# USB_Host_Hub_TypeC_DRP.net
KiCad netlist of a schematic drawn in Altium Designer
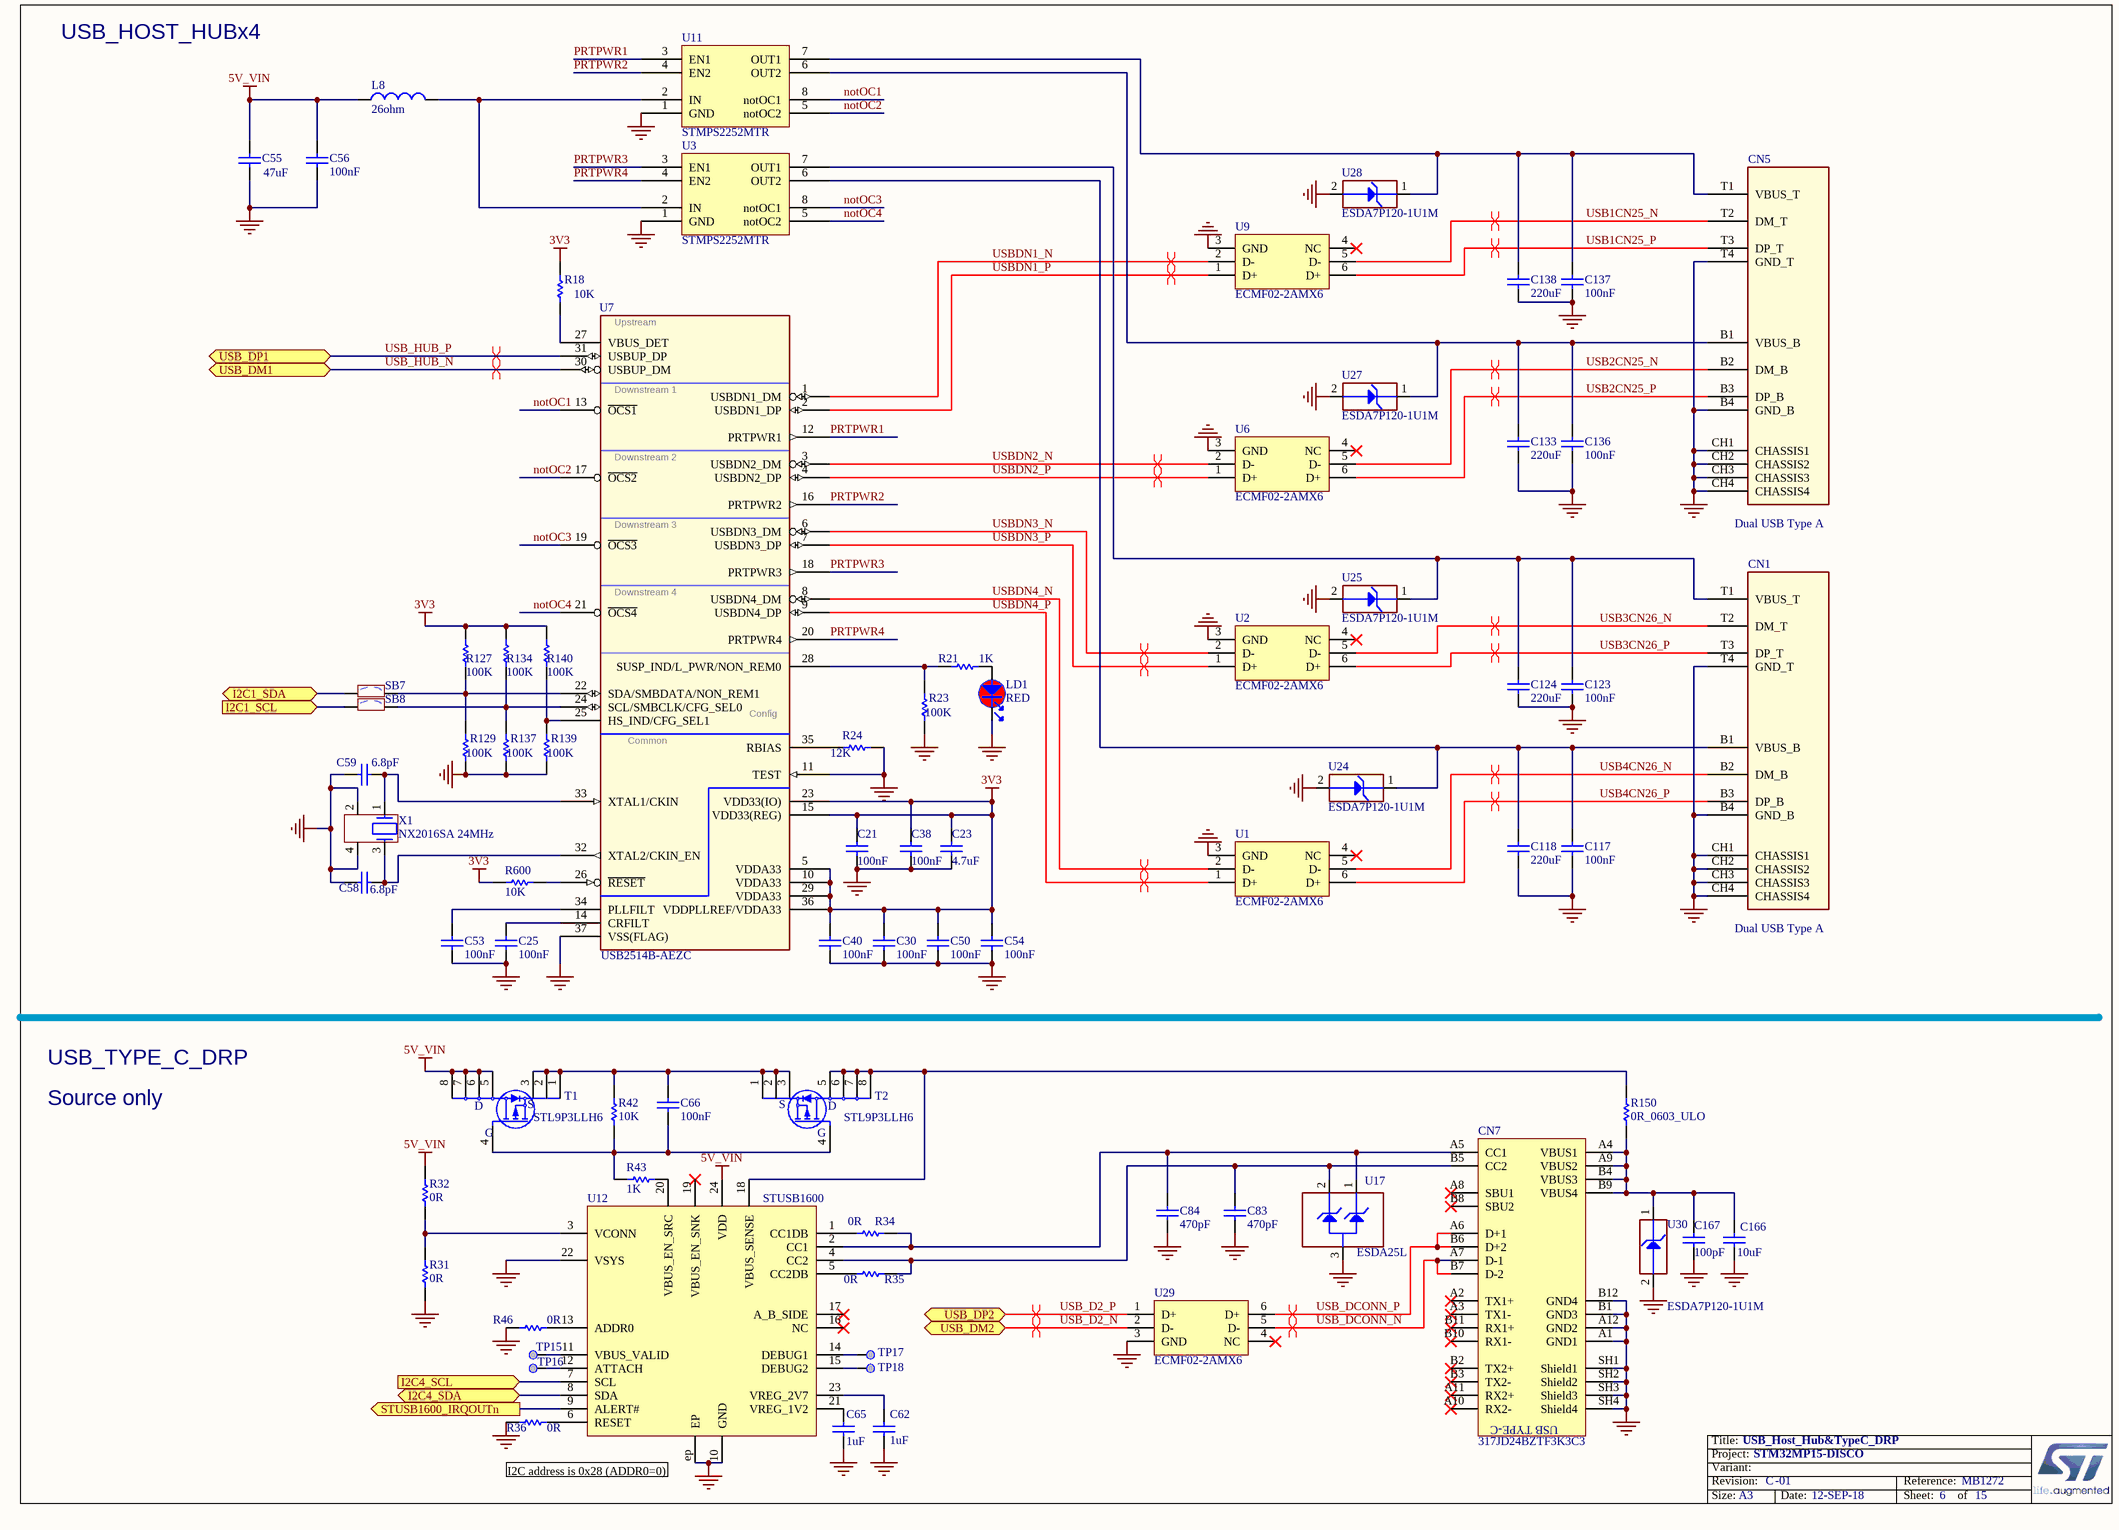
[diagram p0: USB_Host_Hub&TypeC_DRP.SchDoc]

(export (version "E")
  (design (tool "Eeschema 10.0.6"))
  (components
    (comp (ref "C21")
      (value "100nF")
      (footprint "C0402")
      (description "Capacitor, MLCC, 100nF, 16V, X7R, 10%, 0402, T=0,5mm")
      (fields
        (field (name "INTERNAL_PART_NUMBER") "MCD-00102")
        (field (name "MANUFACTURER_PART_NUMBER") "CC0402KRX7R7BB104")
        (field (name "PROVIDED_BY") "SUBCO")
      )
      (libsource (lib "MCD_PARTS_database") (part "Capacitor"))
    )
    (comp (ref "C23")
      (value "4.7uF")
      (footprint "C0402")
      (description "Capacitor, MLCC, 4.7uF, 6V3, X5R, 20%, 0402, T=0,5mm")
      (fields
        (field (name "INTERNAL_PART_NUMBER") "MCD-01356")
        (field (name "MANUFACTURER_PART_NUMBER") "GRM155R60J475ME47")
        (field (name "PROVIDED_BY") "SUBCO")
      )
      (libsource (lib "MCD_PARTS_database") (part "Capacitor"))
    )
    (comp (ref "C25")
      (value "100nF")
      (footprint "C0402")
      (description "Capacitor, MLCC, 100nF, 16V, X7R, 10%, 0402, T=0,5mm")
      (fields
        (field (name "INTERNAL_PART_NUMBER") "MCD-00102")
        (field (name "MANUFACTURER_PART_NUMBER") "CC0402KRX7R7BB104")
        (field (name "PROVIDED_BY") "SUBCO")
      )
      (libsource (lib "MCD_PARTS_database") (part "Capacitor"))
    )
    (comp (ref "C30")
      (value "100nF")
      (footprint "C0402")
      (description "Capacitor, MLCC, 100nF, 16V, X7R, 10%, 0402, T=0,5mm")
      (fields
        (field (name "INTERNAL_PART_NUMBER") "MCD-00102")
        (field (name "MANUFACTURER_PART_NUMBER") "CC0402KRX7R7BB104")
        (field (name "PROVIDED_BY") "SUBCO")
      )
      (libsource (lib "MCD_PARTS_database") (part "Capacitor"))
    )
    (comp (ref "C38")
      (value "100nF")
      (footprint "C0402")
      (description "Capacitor, MLCC, 100nF, 16V, X7R, 10%, 0402, T=0,5mm")
      (fields
        (field (name "INTERNAL_PART_NUMBER") "MCD-00102")
        (field (name "MANUFACTURER_PART_NUMBER") "CC0402KRX7R7BB104")
        (field (name "PROVIDED_BY") "SUBCO")
      )
      (libsource (lib "MCD_PARTS_database") (part "Capacitor"))
    )
    (comp (ref "C40")
      (value "100nF")
      (footprint "C0402")
      (description "Capacitor, MLCC, 100nF, 16V, X7R, 10%, 0402, T=0,5mm")
      (fields
        (field (name "INTERNAL_PART_NUMBER") "MCD-00102")
        (field (name "MANUFACTURER_PART_NUMBER") "CC0402KRX7R7BB104")
        (field (name "PROVIDED_BY") "SUBCO")
      )
      (libsource (lib "MCD_PARTS_database") (part "Capacitor"))
    )
    (comp (ref "C50")
      (value "100nF")
      (footprint "C0402")
      (description "Capacitor, MLCC, 100nF, 16V, X7R, 10%, 0402, T=0,5mm")
      (fields
        (field (name "INTERNAL_PART_NUMBER") "MCD-00102")
        (field (name "MANUFACTURER_PART_NUMBER") "CC0402KRX7R7BB104")
        (field (name "PROVIDED_BY") "SUBCO")
      )
      (libsource (lib "MCD_PARTS_database") (part "Capacitor"))
    )
    (comp (ref "C53")
      (value "100nF")
      (footprint "C0402")
      (description "Capacitor, MLCC, 100nF, 16V, X7R, 10%, 0402, T=0,5mm")
      (fields
        (field (name "INTERNAL_PART_NUMBER") "MCD-00102")
        (field (name "MANUFACTURER_PART_NUMBER") "CC0402KRX7R7BB104")
        (field (name "PROVIDED_BY") "SUBCO")
      )
      (libsource (lib "MCD_PARTS_database") (part "Capacitor"))
    )
    (comp (ref "C54")
      (value "100nF")
      (footprint "C0402")
      (description "Capacitor, MLCC, 100nF, 16V, X7R, 10%, 0402, T=0,5mm")
      (fields
        (field (name "INTERNAL_PART_NUMBER") "MCD-00102")
        (field (name "MANUFACTURER_PART_NUMBER") "CC0402KRX7R7BB104")
        (field (name "PROVIDED_BY") "SUBCO")
      )
      (libsource (lib "MCD_PARTS_database") (part "Capacitor"))
    )
    (comp (ref "C55")
      (value "47uF")
      (footprint "C0805")
      (description "Capacitor, MLCC, 47uF, 10V, X5R, 20%, 0805, T=1,25mm")
      (fields
        (field (name "INTERNAL_PART_NUMBER") "MCD-00204")
        (field (name "MANUFACTURER_PART_NUMBER") "GRM21BR61A476ME15K")
        (field (name "PROVIDED_BY") "SUBCO")
      )
      (libsource (lib "MCD_PARTS_database") (part "Capacitor"))
    )
    (comp (ref "C56")
      (value "100nF")
      (footprint "C0402")
      (description "Capacitor, MLCC, 100nF, 16V, X7R, 10%, 0402, T=0,5mm")
      (fields
        (field (name "INTERNAL_PART_NUMBER") "MCD-00102")
        (field (name "MANUFACTURER_PART_NUMBER") "CC0402KRX7R7BB104")
        (field (name "PROVIDED_BY") "SUBCO")
      )
      (libsource (lib "MCD_PARTS_database") (part "Capacitor"))
    )
    (comp (ref "C58")
      (value "6.8pF")
      (footprint "C0402")
      (description "Capacitor, MLCC, 6.8pF, 50V, NPO, +-0.25pF, 0402, T=0.5mm")
      (fields
        (field (name "INTERNAL_PART_NUMBER") "MCD-00674")
        (field (name "MANUFACTURER_PART_NUMBER") "CC0402CRNPO9BN6R8")
        (field (name "PROVIDED_BY") "SUBCO")
      )
      (libsource (lib "MCD_PARTS_database") (part "Capacitor"))
    )
    (comp (ref "C59")
      (value "6.8pF")
      (footprint "C0402")
      (description "Capacitor, MLCC, 6.8pF, 50V, NPO, +-0.25pF, 0402, T=0.5mm")
      (fields
        (field (name "INTERNAL_PART_NUMBER") "MCD-00674")
        (field (name "MANUFACTURER_PART_NUMBER") "CC0402CRNPO9BN6R8")
        (field (name "PROVIDED_BY") "SUBCO")
      )
      (libsource (lib "MCD_PARTS_database") (part "Capacitor"))
    )
    (comp (ref "C62")
      (value "1uF")
      (footprint "C0402")
      (description "Capacitor, MLCC, 1uF, 6V3, X5R, 10%, 0402, T=0,5mm")
      (fields
        (field (name "INTERNAL_PART_NUMBER") "MCD-00095")
        (field (name "MANUFACTURER_PART_NUMBER") "GRM155R61E105KA12")
        (field (name "PROVIDED_BY") "SUBCO")
      )
      (libsource (lib "MCD_PARTS_database") (part "Capacitor"))
    )
    (comp (ref "C65")
      (value "1uF")
      (footprint "C0402")
      (description "Capacitor, MLCC, 1uF, 6V3, X5R, 10%, 0402, T=0,5mm")
      (fields
        (field (name "INTERNAL_PART_NUMBER") "MCD-00095")
        (field (name "MANUFACTURER_PART_NUMBER") "GRM155R61E105KA12")
        (field (name "PROVIDED_BY") "SUBCO")
      )
      (libsource (lib "MCD_PARTS_database") (part "Capacitor"))
    )
    (comp (ref "C66")
      (value "100nF")
      (footprint "C0402")
      (description "Capacitor, MLCC, 100nF, 16V, X7R, 10%, 0402, T=0,5mm")
      (fields
        (field (name "INTERNAL_PART_NUMBER") "MCD-00102")
        (field (name "MANUFACTURER_PART_NUMBER") "CC0402KRX7R7BB104")
        (field (name "PROVIDED_BY") "SUBCO")
      )
      (libsource (lib "MCD_PARTS_database") (part "Capacitor"))
    )
    (comp (ref "C83")
      (value "470pF")
      (footprint "C0402")
      (description "Capacitor, MLCC, 470pF, 50V, NPO, 5%, 0402, T=0,5mm")
      (fields
        (field (name "INTERNAL_PART_NUMBER") "MCD-00724")
        (field (name "MANUFACTURER_PART_NUMBER") "CC0402JRNPO9BN471")
        (field (name "PROVIDED_BY") "SUBCO")
      )
      (libsource (lib "MCD_PARTS_database") (part "Capacitor"))
    )
    (comp (ref "C84")
      (value "470pF")
      (footprint "C0402")
      (description "Capacitor, MLCC, 470pF, 50V, NPO, 5%, 0402, T=0,5mm")
      (fields
        (field (name "INTERNAL_PART_NUMBER") "MCD-00724")
        (field (name "MANUFACTURER_PART_NUMBER") "CC0402JRNPO9BN471")
        (field (name "PROVIDED_BY") "SUBCO")
      )
      (libsource (lib "MCD_PARTS_database") (part "Capacitor"))
    )
    (comp (ref "C117")
      (value "100nF")
      (footprint "C0402")
      (description "Capacitor, MLCC, 100nF, 16V, X7R, 10%, 0402, T=0,5mm")
      (fields
        (field (name "INTERNAL_PART_NUMBER") "MCD-00102")
        (field (name "MANUFACTURER_PART_NUMBER") "CC0402KRX7R7BB104")
        (field (name "PROVIDED_BY") "SUBCO")
      )
      (libsource (lib "MCD_PARTS_database") (part "Capacitor"))
    )
    (comp (ref "C118")
      (value "220uF")
      (footprint "C1206_H1P6")
      (description "Capacitor, MLCC, 220uF, 6V3, X5R, 20%, 1206, T=1,6mm")
      (fields
        (field (name "INTERNAL_PART_NUMBER") "MCD-00104")
        (field (name "MANUFACTURER_PART_NUMBER") "GRM31CR60J227ME11")
        (field (name "PROVIDED_BY") "SUBCO")
      )
      (libsource (lib "MCD_PARTS_database") (part "Capacitor"))
    )
    (comp (ref "C123")
      (value "100nF")
      (footprint "C0402")
      (description "Capacitor, MLCC, 100nF, 16V, X7R, 10%, 0402, T=0,5mm")
      (fields
        (field (name "INTERNAL_PART_NUMBER") "MCD-00102")
        (field (name "MANUFACTURER_PART_NUMBER") "CC0402KRX7R7BB104")
        (field (name "PROVIDED_BY") "SUBCO")
      )
      (libsource (lib "MCD_PARTS_database") (part "Capacitor"))
    )
    (comp (ref "C124")
      (value "220uF")
      (footprint "C1206_H1P6")
      (description "Capacitor, MLCC, 220uF, 6V3, X5R, 20%, 1206, T=1,6mm")
      (fields
        (field (name "INTERNAL_PART_NUMBER") "MCD-00104")
        (field (name "MANUFACTURER_PART_NUMBER") "GRM31CR60J227ME11")
        (field (name "PROVIDED_BY") "SUBCO")
      )
      (libsource (lib "MCD_PARTS_database") (part "Capacitor"))
    )
    (comp (ref "C133")
      (value "220uF")
      (footprint "C1206_H1P6")
      (description "Capacitor, MLCC, 220uF, 6V3, X5R, 20%, 1206, T=1,6mm")
      (fields
        (field (name "INTERNAL_PART_NUMBER") "MCD-00104")
        (field (name "MANUFACTURER_PART_NUMBER") "GRM31CR60J227ME11")
        (field (name "PROVIDED_BY") "SUBCO")
      )
      (libsource (lib "MCD_PARTS_database") (part "Capacitor"))
    )
    (comp (ref "C136")
      (value "100nF")
      (footprint "C0402")
      (description "Capacitor, MLCC, 100nF, 16V, X7R, 10%, 0402, T=0,5mm")
      (fields
        (field (name "INTERNAL_PART_NUMBER") "MCD-00102")
        (field (name "MANUFACTURER_PART_NUMBER") "CC0402KRX7R7BB104")
        (field (name "PROVIDED_BY") "SUBCO")
      )
      (libsource (lib "MCD_PARTS_database") (part "Capacitor"))
    )
    (comp (ref "C137")
      (value "100nF")
      (footprint "C0402")
      (description "Capacitor, MLCC, 100nF, 16V, X7R, 10%, 0402, T=0,5mm")
      (fields
        (field (name "INTERNAL_PART_NUMBER") "MCD-00102")
        (field (name "MANUFACTURER_PART_NUMBER") "CC0402KRX7R7BB104")
        (field (name "PROVIDED_BY") "SUBCO")
      )
      (libsource (lib "MCD_PARTS_database") (part "Capacitor"))
    )
    (comp (ref "C138")
      (value "220uF")
      (footprint "C1206_H1P6")
      (description "Capacitor, MLCC, 220uF, 6V3, X5R, 20%, 1206, T=1,6mm")
      (fields
        (field (name "INTERNAL_PART_NUMBER") "MCD-00104")
        (field (name "MANUFACTURER_PART_NUMBER") "GRM31CR60J227ME11")
        (field (name "PROVIDED_BY") "SUBCO")
      )
      (libsource (lib "MCD_PARTS_database") (part "Capacitor"))
    )
    (comp (ref "C166")
      (value "10uF")
      (footprint "C0805")
      (description "Capacitor, MLCC, 10uF, 25V, X5R, 10%, 0805, T=0,85mm")
      (fields
        (field (name "INTERNAL_PART_NUMBER") "MCD-00014")
        (field (name "MANUFACTURER_PART_NUMBER") "CC0805KRX5R8BB106")
        (field (name "PROVIDED_BY") "SUBCO")
      )
      (libsource (lib "MCD_PARTS_database") (part "Capacitor"))
    )
    (comp (ref "C167")
      (value "100pF")
      (footprint "C0402")
      (description "Capacitor, MLCC, 100pF, 50V, NPO, 5%, 0402, T=0,5mm")
      (fields
        (field (name "INTERNAL_PART_NUMBER") "MCD-00205")
        (field (name "MANUFACTURER_PART_NUMBER") "CC0402JRNPO9BN101")
        (field (name "PROVIDED_BY") "SUBCO")
      )
      (libsource (lib "MCD_PARTS_database") (part "Capacitor"))
    )
    (comp (ref "CN1")
      (value "Dual USB Type A")
      (footprint "CON_DUAL-USB-TYPE-A_CONEXCON_5600-3081")
      (description "USB-Receptacle,Dual-Type-A, RA, TH, Height 15.5mm")
      (fields
        (field (name "INTERNAL_PART_NUMBER") "MCD-00109")
        (field (name "MANUFACTURER_PART_NUMBER") "5600-3081")
        (field (name "PROVIDED_BY") "SUBCO")
      )
      (libsource (lib "MCD_PARTS_database") (part "USB_DUAL_TYPEA_5600-3081"))
    )
    (comp (ref "CN5")
      (value "Dual USB Type A")
      (footprint "CON_DUAL-USB-TYPE-A_CONEXCON_5600-3081")
      (description "USB-Receptacle,Dual-Type-A, RA, TH, Height 15.5mm")
      (fields
        (field (name "INTERNAL_PART_NUMBER") "MCD-00109")
        (field (name "MANUFACTURER_PART_NUMBER") "5600-3081")
        (field (name "PROVIDED_BY") "SUBCO")
      )
      (libsource (lib "MCD_PARTS_database") (part "USB_DUAL_TYPEA_5600-3081"))
    )
    (comp (ref "CN7")
      (value "317JD24BZTF3K3C3")
      (footprint "CON_USB-TYPEC_COXOC_317JD24BZTF3K3C3")
      (description "USB tyce C certified receptacle for 1.6mm pcb height")
      (fields
        (field (name "INTERNAL_PART_NUMBER") "MCD-01108")
        (field (name "MANUFACTURER") "CHANT SINCERE (COXOC)")
        (field (name "PROVIDED_BY") "SUBCO")
      )
      (libsource (lib "MCD_PARTS_database") (part "USB_TYPE_C_Receptacle_317JD24BZTF3K3C3"))
    )
    (comp (ref "L8")
      (value "26ohm")
      (footprint "FIL_0603_H0P65")
      (description "Bead,26R at 100Mhz,6A,0603")
      (fields
        (field (name "INTERNAL_PART_NUMBER") "MCD-00305")
        (field (name "MANUFACTURER_PART_NUMBER") "BLM18KG260TN1")
        (field (name "PROVIDED_BY") "SUBCO")
      )
      (libsource (lib "MCD_PARTS_database") (part "BEAD"))
    )
    (comp (ref "LD1")
      (value "RED")
      (footprint "LED_0603_RED")
      (description "LED, Red, 0603")
      (fields
        (field (name "INTERNAL_PART_NUMBER") "MCD-00049")
        (field (name "MANUFACTURER_PART_NUMBER") "19-213-R6C-AP1Q2B/3T")
        (field (name "PROVIDED_BY") "SUBCO")
      )
      (libsource (lib "MCD_PARTS_database") (part "LED_red"))
    )
    (comp (ref "R18")
      (value "10K")
      (footprint "R0402")
      (description "Resistor,10K,0402,1%,1/16W")
      (fields
        (field (name "INTERNAL_PART_NUMBER") "MCD-00053")
        (field (name "MANUFACTURER_PART_NUMBER") "RC0402FR-0710KL")
        (field (name "PROVIDED_BY") "SUBCO")
      )
      (libsource (lib "MCD_PARTS_database") (part "Resistor"))
    )
    (comp (ref "R21")
      (value "1K")
      (footprint "R0402")
      (description "Resistor,1K,0402,1%,1/16W")
      (fields
        (field (name "INTERNAL_PART_NUMBER") "MCD-00061")
        (field (name "MANUFACTURER_PART_NUMBER") "RC0402FR-071KL")
        (field (name "PROVIDED_BY") "SUBCO")
      )
      (libsource (lib "MCD_PARTS_database") (part "Resistor"))
    )
    (comp (ref "R23")
      (value "100K")
      (footprint "R0402")
      (description "Resistor,100K,0402,1%,1/16W")
      (fields
        (field (name "INTERNAL_PART_NUMBER") "MCD-00059")
        (field (name "MANUFACTURER_PART_NUMBER") "RC0402FR-07100KL")
        (field (name "PROVIDED_BY") "SUBCO")
      )
      (libsource (lib "MCD_PARTS_database") (part "Resistor"))
    )
    (comp (ref "R24")
      (value "12K")
      (footprint "R0402")
      (description "Resistor,12K,0402,1%,1/16W")
      (fields
        (field (name "INTERNAL_PART_NUMBER") "MCD-00187")
        (field (name "MANUFACTURER_PART_NUMBER") "RC0402FR-0712KL")
        (field (name "PROVIDED_BY") "SUBCO")
      )
      (libsource (lib "MCD_PARTS_database") (part "Resistor"))
    )
    (comp (ref "R31")
      (value "0R")
      (footprint "R0402")
      (description "Resistor,0R,0402,5%,1/16W")
      (fields
        (field (name "INTERNAL_PART_NUMBER") "MCD-00052")
        (field (name "MANUFACTURER_PART_NUMBER") "RC0402JR-070RL")
        (field (name "PROVIDED_BY") "SUBCO")
      )
      (libsource (lib "MCD_PARTS_database") (part "Resistor"))
    )
    (comp (ref "R32")
      (value "0R")
      (footprint "R0402")
      (description "Resistor,0R,0402,5%,1/16W")
      (fields
        (field (name "INTERNAL_PART_NUMBER") "MCD-00052")
        (field (name "MANUFACTURER_PART_NUMBER") "RC0402JR-070RL")
        (field (name "PROVIDED_BY") "SUBCO")
      )
      (libsource (lib "MCD_PARTS_database") (part "Resistor"))
    )
    (comp (ref "R34")
      (value "0R")
      (footprint "R0402")
      (description "Resistor,0R,0402,5%,1/16W")
      (fields
        (field (name "INTERNAL_PART_NUMBER") "MCD-00052")
        (field (name "MANUFACTURER_PART_NUMBER") "RC0402JR-070RL")
        (field (name "PROVIDED_BY") "SUBCO")
      )
      (libsource (lib "MCD_PARTS_database") (part "Resistor"))
    )
    (comp (ref "R35")
      (value "0R")
      (footprint "R0402")
      (description "Resistor,0R,0402,5%,1/16W")
      (fields
        (field (name "INTERNAL_PART_NUMBER") "MCD-00052")
        (field (name "MANUFACTURER_PART_NUMBER") "RC0402JR-070RL")
        (field (name "PROVIDED_BY") "SUBCO")
      )
      (libsource (lib "MCD_PARTS_database") (part "Resistor"))
    )
    (comp (ref "R36")
      (value "0R")
      (footprint "R0402")
      (description "Resistor,0R,0402,5%,1/16W")
      (fields
        (field (name "INTERNAL_PART_NUMBER") "MCD-00052")
        (field (name "MANUFACTURER_PART_NUMBER") "RC0402JR-070RL")
        (field (name "PROVIDED_BY") "SUBCO")
      )
      (libsource (lib "MCD_PARTS_database") (part "Resistor"))
    )
    (comp (ref "R42")
      (value "10K")
      (footprint "R0402")
      (description "Resistor,10K,0402,1%,1/16W")
      (fields
        (field (name "INTERNAL_PART_NUMBER") "MCD-00053")
        (field (name "MANUFACTURER_PART_NUMBER") "RC0402FR-0710KL")
        (field (name "PROVIDED_BY") "SUBCO")
      )
      (libsource (lib "MCD_PARTS_database") (part "Resistor"))
    )
    (comp (ref "R43")
      (value "1K")
      (footprint "R0402")
      (description "Resistor,1K,0402,1%,1/16W")
      (fields
        (field (name "INTERNAL_PART_NUMBER") "MCD-00061")
        (field (name "MANUFACTURER_PART_NUMBER") "RC0402FR-071KL")
        (field (name "PROVIDED_BY") "SUBCO")
      )
      (libsource (lib "MCD_PARTS_database") (part "Resistor"))
    )
    (comp (ref "R46")
      (value "0R")
      (footprint "R0402")
      (description "Resistor,0R,0402,5%,1/16W")
      (fields
        (field (name "INTERNAL_PART_NUMBER") "MCD-00052")
        (field (name "MANUFACTURER_PART_NUMBER") "RC0402JR-070RL")
        (field (name "PROVIDED_BY") "SUBCO")
      )
      (libsource (lib "MCD_PARTS_database") (part "Resistor"))
    )
    (comp (ref "R127")
      (value "100K")
      (footprint "R0402")
      (description "Resistor,100K,0402,1%,1/16W")
      (fields
        (field (name "INTERNAL_PART_NUMBER") "MCD-00059")
        (field (name "MANUFACTURER_PART_NUMBER") "RC0402FR-07100KL")
        (field (name "PROVIDED_BY") "SUBCO")
      )
      (libsource (lib "MCD_PARTS_database") (part "Resistor"))
    )
    (comp (ref "R129")
      (value "100K")
      (footprint "R0402")
      (description "Resistor,100K,0402,1%,1/16W")
      (fields
        (field (name "INTERNAL_PART_NUMBER") "MCD-00059")
        (field (name "MANUFACTURER_PART_NUMBER") "RC0402FR-07100KL")
        (field (name "PROVIDED_BY") "SUBCO")
      )
      (libsource (lib "MCD_PARTS_database") (part "Resistor"))
    )
    (comp (ref "R134")
      (value "100K")
      (footprint "R0402")
      (description "Resistor,100K,0402,1%,1/16W")
      (fields
        (field (name "INTERNAL_PART_NUMBER") "MCD-00059")
        (field (name "MANUFACTURER_PART_NUMBER") "RC0402FR-07100KL")
        (field (name "PROVIDED_BY") "SUBCO")
      )
      (libsource (lib "MCD_PARTS_database") (part "Resistor"))
    )
    (comp (ref "R137")
      (value "100K")
      (footprint "R0402")
      (description "Resistor,100K,0402,1%,1/16W")
      (fields
        (field (name "INTERNAL_PART_NUMBER") "MCD-00059")
        (field (name "MANUFACTURER_PART_NUMBER") "RC0402FR-07100KL")
        (field (name "PROVIDED_BY") "SUBCO")
      )
      (libsource (lib "MCD_PARTS_database") (part "Resistor"))
    )
    (comp (ref "R139")
      (value "100K")
      (footprint "R0402")
      (description "Resistor,100K,0402,1%,1/16W")
      (fields
        (field (name "INTERNAL_PART_NUMBER") "MCD-00059")
        (field (name "MANUFACTURER_PART_NUMBER") "RC0402FR-07100KL")
        (field (name "PROVIDED_BY") "SUBCO")
      )
      (libsource (lib "MCD_PARTS_database") (part "Resistor"))
    )
    (comp (ref "R140")
      (value "100K")
      (footprint "R0402")
      (description "Resistor,100K,0402,1%,1/16W")
      (fields
        (field (name "INTERNAL_PART_NUMBER") "MCD-00059")
        (field (name "MANUFACTURER_PART_NUMBER") "RC0402FR-07100KL")
        (field (name "PROVIDED_BY") "SUBCO")
      )
      (libsource (lib "MCD_PARTS_database") (part "Resistor"))
    )
    (comp (ref "R150")
      (value "0R_0603_ULO")
      (footprint "R0603")
      (description "Resistor,0R,0603,ULO")
      (fields
        (field (name "INTERNAL_PART_NUMBER") "MCD-00181")
        (field (name "MANUFACTURER_PART_NUMBER") "PMR03EZPJ000")
        (field (name "PROVIDED_BY") "SUBCO")
      )
      (libsource (lib "MCD_PARTS_database") (part "Resistor"))
    )
    (comp (ref "R600")
      (value "10K")
      (footprint "R0402")
      (description "Resistor,10K,0402,1%,1/16W")
      (fields
        (field (name "INTERNAL_PART_NUMBER") "MCD-00053")
        (field (name "MANUFACTURER_PART_NUMBER") "RC0402FR-0710KL")
        (field (name "PROVIDED_BY") "SUBCO")
      )
      (libsource (lib "MCD_PARTS_database") (part "Resistor"))
    )
    (comp (ref "SB7")
      (value "SB_OFF")
      (footprint "SOLDER-BRIDGE_R0603-0R")
      (description "Solder Bridge OFF")
      (fields
        (field (name "INTERNAL_PART_NUMBER") "MCD-00072")
        (field (name "MANUFACTURER") "YAGEO")
        (field (name "PROVIDED_BY") "SUBCO")
      )
      (libsource (lib "MCD_PARTS_database") (part "SB_OFF"))
    )
    (comp (ref "SB8")
      (value "SB_OFF")
      (footprint "SOLDER-BRIDGE_R0603-0R")
      (description "Solder Bridge OFF")
      (fields
        (field (name "INTERNAL_PART_NUMBER") "MCD-00072")
        (field (name "MANUFACTURER") "YAGEO")
        (field (name "PROVIDED_BY") "SUBCO")
      )
      (libsource (lib "MCD_PARTS_database") (part "SB_OFF"))
    )
    (comp (ref "T1")
      (value "STL9P3LLH6")
      (footprint "MOS_POWERFLAT_3P3X3P3_P065")
      (description "Power Mosfet, P-channel,VDS -30V,RDS 12mohm typ,ID -9A")
      (fields
        (field (name "INTERNAL_PART_NUMBER") "MCD-01126")
        (field (name "MANUFACTURER") "STMICROELECTRONICS")
        (field (name "PROVIDED_BY") "SUBCO with ST control")
      )
      (libsource (lib "MCD_PARTS_database") (part "STL9P3LLH6"))
    )
    (comp (ref "T2")
      (value "STL9P3LLH6")
      (footprint "MOS_POWERFLAT_3P3X3P3_P065")
      (description "Power Mosfet, P-channel,VDS -30V,RDS 12mohm typ,ID -9A")
      (fields
        (field (name "INTERNAL_PART_NUMBER") "MCD-01126")
        (field (name "MANUFACTURER") "STMICROELECTRONICS")
        (field (name "PROVIDED_BY") "SUBCO with ST control")
      )
      (libsource (lib "MCD_PARTS_database") (part "STL9P3LLH6"))
    )
    (comp (ref "TP15")
      (value "Test Point")
      (footprint "TP_SMD_1MM")
      (description "Test Point 1mm")
      (fields
        (field (name "INTERNAL_PART_NUMBER") "MCD-00074")
        (field (name "MANUFACTURER_PART_NUMBER") "n/a")
      )
      (libsource (lib "MCD_PARTS_database") (part "Test Point"))
    )
    (comp (ref "TP16")
      (value "Test Point")
      (footprint "TP_SMD_1MM")
      (description "Test Point 1mm")
      (fields
        (field (name "INTERNAL_PART_NUMBER") "MCD-00074")
        (field (name "MANUFACTURER_PART_NUMBER") "n/a")
      )
      (libsource (lib "MCD_PARTS_database") (part "Test Point"))
    )
    (comp (ref "TP17")
      (value "Test Point")
      (footprint "TP_SMD_1MM")
      (description "Test Point 1mm")
      (fields
        (field (name "INTERNAL_PART_NUMBER") "MCD-00074")
        (field (name "MANUFACTURER_PART_NUMBER") "n/a")
      )
      (libsource (lib "") (part "Test Point_1"))
    )
    (comp (ref "TP18")
      (value "Test Point")
      (footprint "TP_SMD_1MM")
      (description "Test Point 1mm")
      (fields
        (field (name "INTERNAL_PART_NUMBER") "MCD-00074")
        (field (name "MANUFACTURER_PART_NUMBER") "n/a")
      )
      (libsource (lib "") (part "Test Point_1"))
    )
    (comp (ref "U1")
      (value "ECMF02-2AMX6")
      (footprint "ESD_QFN-6L_1P7X1P5_P050")
      (description "Common mode filter with ESD protection for USB 2.0 interface")
      (fields
        (field (name "INTERNAL_PART_NUMBER") "MCD-00649")
        (field (name "MANUFACTURER") "STMICROELECTRONICS")
        (field (name "PROVIDED_BY") "SUBCO with ST control")
      )
      (libsource (lib "") (part "ECMF02-2AMX6_1"))
    )
    (comp (ref "U2")
      (value "ECMF02-2AMX6")
      (footprint "ESD_QFN-6L_1P7X1P5_P050")
      (description "Common mode filter with ESD protection for USB 2.0 interface")
      (fields
        (field (name "INTERNAL_PART_NUMBER") "MCD-00649")
        (field (name "MANUFACTURER") "STMICROELECTRONICS")
        (field (name "PROVIDED_BY") "SUBCO with ST control")
      )
      (libsource (lib "") (part "ECMF02-2AMX6_1"))
    )
    (comp (ref "U3")
      (value "STMPS2252MTR")
      (footprint "ICC_SO8_5X4_P127")
      (description "IC,Dual-Channel-Power-Switch,500mA,100mR,SO8")
      (fields
        (field (name "INTERNAL_PART_NUMBER") "MCD-00123")
        (field (name "MANUFACTURER") "STMICROELECTRONICS")
        (field (name "PROVIDED_BY") "SUBCO with ST control")
      )
      (libsource (lib "MCD_PARTS_database") (part "STMPS2252MTR"))
    )
    (comp (ref "U6")
      (value "ECMF02-2AMX6")
      (footprint "ESD_QFN-6L_1P7X1P5_P050")
      (description "Common mode filter with ESD protection for USB 2.0 interface")
      (fields
        (field (name "INTERNAL_PART_NUMBER") "MCD-00649")
        (field (name "MANUFACTURER") "STMICROELECTRONICS")
        (field (name "PROVIDED_BY") "SUBCO with ST control")
      )
      (libsource (lib "") (part "ECMF02-2AMX6_1"))
    )
    (comp (ref "U7")
      (value "USB2514B-AEZC")
      (footprint "ICC_QFN36-EPAD_6X6_P050")
      (description "USB HUB 2,0 Controller")
      (fields
        (field (name "INTERNAL_PART_NUMBER") "MCD-00145")
        (field (name "MANUFACTURER") "MICROCHIP")
        (field (name "PROVIDED_BY") "SUBCO")
      )
      (libsource (lib "MCD_PARTS_database") (part "USB2514B-AEZC"))
    )
    (comp (ref "U9")
      (value "ECMF02-2AMX6")
      (footprint "ESD_QFN-6L_1P7X1P5_P050")
      (description "Common mode filter with ESD protection for USB 2.0 interface")
      (fields
        (field (name "INTERNAL_PART_NUMBER") "MCD-00649")
        (field (name "MANUFACTURER") "STMICROELECTRONICS")
        (field (name "PROVIDED_BY") "SUBCO with ST control")
      )
      (libsource (lib "") (part "ECMF02-2AMX6_1"))
    )
    (comp (ref "U11")
      (value "STMPS2252MTR")
      (footprint "ICC_SO8_5X4_P127")
      (description "IC,Dual-Channel-Power-Switch,500mA,100mR,SO8")
      (fields
        (field (name "INTERNAL_PART_NUMBER") "MCD-00123")
        (field (name "MANUFACTURER") "STMICROELECTRONICS")
        (field (name "PROVIDED_BY") "SUBCO with ST control")
      )
      (libsource (lib "MCD_PARTS_database") (part "STMPS2252MTR"))
    )
    (comp (ref "U12")
      (value "STUSB1600")
      (footprint "ICC_QFN24-EPAD_4X4_P050")
      (description "USB Type-C controller with VCONN switch")
      (fields
        (field (name "INTERNAL_PART_NUMBER") "MCD-00676")
        (field (name "MANUFACTURER_PART_NUMBER") "STUSB1600AQTR")
        (field (name "PROVIDED_BY") "SUBCO with ST control")
      )
      (libsource (lib "MCD_PARTS_database") (part "STUSB1600QTR"))
    )
    (comp (ref "U17")
      (value "ESDA25L")
      (footprint "ESD_SOT23")
      (description "DUAL TRANSIL ARRAY FOR ESD PROTECTION")
      (fields
        (field (name "INTERNAL_PART_NUMBER") "MCD-01125")
        (field (name "MANUFACTURER") "STMICROELECTRONICS")
        (field (name "PROVIDED_BY") "SUBCO with ST control")
      )
      (libsource (lib "MCD_PARTS_database") (part "ESDA25L"))
    )
    (comp (ref "U24")
      (value "ESDA7P120-1U1M")
      (footprint "ESD_QFN1610_2N_1K_2A")
      (description "High power transient voltage suppressor")
      (fields
        (field (name "INTERNAL_PART_NUMBER") "MCD-01026")
        (field (name "MANUFACTURER") "STMICROELECTRONICS")
        (field (name "PROVIDED_BY") "SUBCO with ST control")
      )
      (libsource (lib "MCD_PARTS_database") (part "ESD-TRANSIL"))
    )
    (comp (ref "U25")
      (value "ESDA7P120-1U1M")
      (footprint "ESD_QFN1610_2N_1K_2A")
      (description "High power transient voltage suppressor")
      (fields
        (field (name "INTERNAL_PART_NUMBER") "MCD-01026")
        (field (name "MANUFACTURER") "STMICROELECTRONICS")
        (field (name "PROVIDED_BY") "SUBCO with ST control")
      )
      (libsource (lib "MCD_PARTS_database") (part "ESD-TRANSIL"))
    )
    (comp (ref "U27")
      (value "ESDA7P120-1U1M")
      (footprint "ESD_QFN1610_2N_1K_2A")
      (description "High power transient voltage suppressor")
      (fields
        (field (name "INTERNAL_PART_NUMBER") "MCD-01026")
        (field (name "MANUFACTURER") "STMICROELECTRONICS")
        (field (name "PROVIDED_BY") "SUBCO with ST control")
      )
      (libsource (lib "MCD_PARTS_database") (part "ESD-TRANSIL"))
    )
    (comp (ref "U28")
      (value "ESDA7P120-1U1M")
      (footprint "ESD_QFN1610_2N_1K_2A")
      (description "High power transient voltage suppressor")
      (fields
        (field (name "INTERNAL_PART_NUMBER") "MCD-01026")
        (field (name "MANUFACTURER") "STMICROELECTRONICS")
        (field (name "PROVIDED_BY") "SUBCO with ST control")
      )
      (libsource (lib "MCD_PARTS_database") (part "ESD-TRANSIL"))
    )
    (comp (ref "U29")
      (value "ECMF02-2AMX6")
      (footprint "ESD_QFN-6L_1P7X1P5_P050")
      (description "Common mode filter with ESD protection for USB 2.0 interface")
      (fields
        (field (name "INTERNAL_PART_NUMBER") "MCD-00649")
        (field (name "MANUFACTURER") "STMICROELECTRONICS")
        (field (name "PROVIDED_BY") "SUBCO with ST control")
      )
      (libsource (lib "MCD_PARTS_database") (part "ECMF02-2AMX6"))
    )
    (comp (ref "U30")
      (value "ESDA7P120-1U1M")
      (footprint "ESD_QFN1610_2N_1K_2A")
      (description "High power transient voltage suppressor")
      (fields
        (field (name "INTERNAL_PART_NUMBER") "MCD-01026")
        (field (name "MANUFACTURER") "STMICROELECTRONICS")
        (field (name "PROVIDED_BY") "SUBCO with ST control")
      )
      (libsource (lib "") (part "ESD-TRANSIL_1"))
    )
    (comp (ref "X1")
      (value "NX2016SA 24MHz")
      (footprint "CRY_NX2016SA_4P")
      (description "Crystal 24MHz, 6pF, +-20ppm, 80ohms max, SMD")
      (fields
        (field (name "INTERNAL_PART_NUMBER") "MCD-01036")
        (field (name "MANUFACTURER_PART_NUMBER") "NX2016SA 24MHz EXS00A-CS10820")
        (field (name "PROVIDED_BY") "SUBCO")
      )
      (libsource (lib "MCD_PARTS_database") (part "XTAL_4_PINS"))
    )
  )
  (nets
    (net (code "1") (name "/I2C1_SCL") (class "Default")
      (node (ref "SB8") (pin "1") (pinfunction "1_1") (pintype "passive"))
    )
    (net (code "2") (name "/I2C1_SDA") (class "Default")
      (node (ref "SB7") (pin "1") (pinfunction "1_1") (pintype "passive"))
    )
    (net (code "3") (name "/I2C4_SCL") (class "Default")
      (node (ref "U12") (pin "7") (pinfunction "SCL_7") (pintype "passive"))
    )
    (net (code "4") (name "/I2C4_SDA") (class "Default")
      (node (ref "U12") (pin "8") (pinfunction "SDA_8") (pintype "passive"))
    )
    (net (code "5") (name "/PRTPWR1") (class "Default")
      (node (ref "U11") (pin "3") (pinfunction "EN1_3") (pintype "passive"))
      (node (ref "U7") (pin "12") (pinfunction "PRTPWR1_12") (pintype "output"))
    )
    (net (code "6") (name "/PRTPWR2") (class "Default")
      (node (ref "U11") (pin "4") (pinfunction "EN2_4") (pintype "passive"))
      (node (ref "U7") (pin "16") (pinfunction "PRTPWR2_16") (pintype "output"))
    )
    (net (code "7") (name "/PRTPWR3") (class "Default")
      (node (ref "U3") (pin "3") (pinfunction "EN1_3") (pintype "passive"))
      (node (ref "U7") (pin "18") (pinfunction "PRTPWR3_18") (pintype "output"))
    )
    (net (code "8") (name "/PRTPWR4") (class "Default")
      (node (ref "U3") (pin "4") (pinfunction "EN2_4") (pintype "passive"))
      (node (ref "U7") (pin "20") (pinfunction "PRTPWR4_20") (pintype "output"))
    )
    (net (code "9") (name "/STUSB1600_IRQOUTn") (class "Default")
      (node (ref "U12") (pin "9") (pinfunction "ALERT#_9") (pintype "passive"))
    )
    (net (code "10") (name "/USB1CN25_N") (class "Default")
      (node (ref "CN5") (pin "T2") (pinfunction "DM_T_T2") (pintype "passive"))
      (node (ref "U9") (pin "5") (pinfunction "D-_5") (pintype "passive"))
    )
    (net (code "11") (name "/USB1CN25_P") (class "Default")
      (node (ref "CN5") (pin "T3") (pinfunction "DP_T_T3") (pintype "passive"))
      (node (ref "U9") (pin "6") (pinfunction "D+_6") (pintype "passive"))
    )
    (net (code "12") (name "/USB2CN25_N") (class "Default")
      (node (ref "CN5") (pin "B2") (pinfunction "DM_B_B2") (pintype "passive"))
      (node (ref "U6") (pin "5") (pinfunction "D-_5") (pintype "passive"))
    )
    (net (code "13") (name "/USB2CN25_P") (class "Default")
      (node (ref "CN5") (pin "B3") (pinfunction "DP_B_B3") (pintype "passive"))
      (node (ref "U6") (pin "6") (pinfunction "D+_6") (pintype "passive"))
    )
    (net (code "14") (name "/USB3CN26_N") (class "Default")
      (node (ref "CN1") (pin "T2") (pinfunction "DM_T_T2") (pintype "passive"))
      (node (ref "U2") (pin "5") (pinfunction "D-_5") (pintype "passive"))
    )
    (net (code "15") (name "/USB3CN26_P") (class "Default")
      (node (ref "CN1") (pin "T3") (pinfunction "DP_T_T3") (pintype "passive"))
      (node (ref "U2") (pin "6") (pinfunction "D+_6") (pintype "passive"))
    )
    (net (code "16") (name "/USB4CN26_N") (class "Default")
      (node (ref "CN1") (pin "B2") (pinfunction "DM_B_B2") (pintype "passive"))
      (node (ref "U1") (pin "5") (pinfunction "D-_5") (pintype "passive"))
    )
    (net (code "17") (name "/USB4CN26_P") (class "Default")
      (node (ref "CN1") (pin "B3") (pinfunction "DP_B_B3") (pintype "passive"))
      (node (ref "U1") (pin "6") (pinfunction "D+_6") (pintype "passive"))
    )
    (net (code "18") (name "/USBDN1_N") (class "Default")
      (node (ref "U7") (pin "1") (pinfunction "USBDN1_DM_1") (pintype "bidirectional"))
      (node (ref "U9") (pin "2") (pinfunction "D-_2") (pintype "passive"))
    )
    (net (code "19") (name "/USBDN1_P") (class "Default")
      (node (ref "U7") (pin "2") (pinfunction "USBDN1_DP_2") (pintype "bidirectional"))
      (node (ref "U9") (pin "1") (pinfunction "D+_1") (pintype "passive"))
    )
    (net (code "20") (name "/USBDN2_N") (class "Default")
      (node (ref "U6") (pin "2") (pinfunction "D-_2") (pintype "passive"))
      (node (ref "U7") (pin "3") (pinfunction "USBDN2_DM_3") (pintype "bidirectional"))
    )
    (net (code "21") (name "/USBDN2_P") (class "Default")
      (node (ref "U6") (pin "1") (pinfunction "D+_1") (pintype "passive"))
      (node (ref "U7") (pin "4") (pinfunction "USBDN2_DP_4") (pintype "bidirectional"))
    )
    (net (code "22") (name "/USBDN3_N") (class "Default")
      (node (ref "U2") (pin "2") (pinfunction "D-_2") (pintype "passive"))
      (node (ref "U7") (pin "6") (pinfunction "USBDN3_DM_6") (pintype "bidirectional"))
    )
    (net (code "23") (name "/USBDN3_P") (class "Default")
      (node (ref "U2") (pin "1") (pinfunction "D+_1") (pintype "passive"))
      (node (ref "U7") (pin "7") (pinfunction "USBDN3_DP_7") (pintype "bidirectional"))
    )
    (net (code "24") (name "/USBDN4_N") (class "Default")
      (node (ref "U1") (pin "2") (pinfunction "D-_2") (pintype "passive"))
      (node (ref "U7") (pin "8") (pinfunction "USBDN4_DM_8") (pintype "bidirectional"))
    )
    (net (code "25") (name "/USBDN4_P") (class "Default")
      (node (ref "U1") (pin "1") (pinfunction "D+_1") (pintype "passive"))
      (node (ref "U7") (pin "9") (pinfunction "USBDN4_DP_9") (pintype "bidirectional"))
    )
    (net (code "26") (name "/USB_D2_N") (class "Default")
      (node (ref "U29") (pin "2") (pinfunction "D-_2") (pintype "passive"))
    )
    (net (code "27") (name "/USB_D2_P") (class "Default")
      (node (ref "U29") (pin "1") (pinfunction "D+_1") (pintype "passive"))
    )
    (net (code "28") (name "/USB_DCONN_N") (class "Default")
      (node (ref "CN7") (pin "A7") (pinfunction "D-1_A7") (pintype "passive"))
      (node (ref "CN7") (pin "B7") (pinfunction "D-2_B7") (pintype "passive"))
      (node (ref "U29") (pin "5") (pinfunction "D-_5") (pintype "passive"))
    )
    (net (code "29") (name "/USB_DCONN_P") (class "Default")
      (node (ref "CN7") (pin "A6") (pinfunction "D+1_A6") (pintype "passive"))
      (node (ref "CN7") (pin "B6") (pinfunction "D+2_B6") (pintype "passive"))
      (node (ref "U29") (pin "6") (pinfunction "D+_6") (pintype "passive"))
    )
    (net (code "30") (name "/USB_HUB_N") (class "Default")
      (node (ref "U7") (pin "30") (pinfunction "USBUP_DM_30") (pintype "bidirectional"))
    )
    (net (code "31") (name "/USB_HUB_P") (class "Default")
      (node (ref "U7") (pin "31") (pinfunction "USBUP_DP_31") (pintype "bidirectional"))
    )
    (net (code "32") (name "/notOC1") (class "Default")
      (node (ref "U11") (pin "8") (pinfunction "notOC1_8") (pintype "passive"))
      (node (ref "U7") (pin "13") (pinfunction "~{OCS1}_13") (pintype "passive"))
    )
    (net (code "33") (name "/notOC2") (class "Default")
      (node (ref "U11") (pin "5") (pinfunction "notOC2_5") (pintype "passive"))
      (node (ref "U7") (pin "17") (pinfunction "~{OCS2}_17") (pintype "passive"))
    )
    (net (code "34") (name "/notOC3") (class "Default")
      (node (ref "U3") (pin "8") (pinfunction "notOC1_8") (pintype "passive"))
      (node (ref "U7") (pin "19") (pinfunction "~{OCS3}_19") (pintype "passive"))
    )
    (net (code "35") (name "/notOC4") (class "Default")
      (node (ref "U3") (pin "5") (pinfunction "notOC2_5") (pintype "passive"))
      (node (ref "U7") (pin "21") (pinfunction "~{OCS4}_21") (pintype "passive"))
    )
    (net (code "36") (name "3V3") (class "Default")
      (node (ref "C21") (pin "2") (pinfunction "2_2") (pintype "passive"))
      (node (ref "C23") (pin "2") (pinfunction "2_2") (pintype "passive"))
      (node (ref "C30") (pin "2") (pinfunction "2_2") (pintype "passive"))
      (node (ref "C38") (pin "2") (pinfunction "2_2") (pintype "passive"))
      (node (ref "C40") (pin "2") (pinfunction "2_2") (pintype "passive"))
      (node (ref "C50") (pin "2") (pinfunction "2_2") (pintype "passive"))
      (node (ref "C54") (pin "2") (pinfunction "2_2") (pintype "passive"))
      (node (ref "R127") (pin "2") (pinfunction "2_2") (pintype "passive"))
      (node (ref "R134") (pin "2") (pinfunction "2_2") (pintype "passive"))
      (node (ref "R140") (pin "2") (pinfunction "2_2") (pintype "passive"))
      (node (ref "R18") (pin "2") (pinfunction "2_2") (pintype "passive"))
      (node (ref "R600") (pin "1") (pinfunction "1_1") (pintype "passive"))
      (node (ref "U7") (pin "10") (pinfunction "VDDA33_10") (pintype "power_in"))
      (node (ref "U7") (pin "15") (pinfunction "VDD33(REG)_15") (pintype "power_in"))
      (node (ref "U7") (pin "23") (pinfunction "VDD33(IO)_23") (pintype "power_in"))
      (node (ref "U7") (pin "29") (pinfunction "VDDA33_29") (pintype "power_in"))
      (node (ref "U7") (pin "36") (pinfunction "VDDPLLREF/VDDA33_36") (pintype "power_in"))
      (node (ref "U7") (pin "5") (pinfunction "VDDA33_5") (pintype "power_in"))
    )
    (net (code "37") (name "5V_VIN") (class "Default")
      (node (ref "C55") (pin "2") (pinfunction "2_2") (pintype "passive"))
      (node (ref "C56") (pin "2") (pinfunction "2_2") (pintype "passive"))
      (node (ref "L8") (pin "1") (pinfunction "1_1") (pintype "passive"))
      (node (ref "R32") (pin "2") (pinfunction "2_2") (pintype "passive"))
      (node (ref "T1") (pin "5") (pinfunction "D_5") (pintype "passive"))
      (node (ref "T1") (pin "6") (pinfunction "D_6") (pintype "passive"))
      (node (ref "T1") (pin "7") (pinfunction "D_7") (pintype "passive"))
      (node (ref "T1") (pin "8") (pinfunction "D_8") (pintype "passive"))
      (node (ref "U12") (pin "24") (pinfunction "VDD_24") (pintype "passive"))
    )
    (net (code "38") (name "GND") (class "Default")
      (node (ref "C117") (pin "1") (pinfunction "1_1") (pintype "passive"))
      (node (ref "C118") (pin "1") (pinfunction "1_1") (pintype "passive"))
      (node (ref "C123") (pin "1") (pinfunction "1_1") (pintype "passive"))
      (node (ref "C124") (pin "1") (pinfunction "1_1") (pintype "passive"))
      (node (ref "C133") (pin "1") (pinfunction "1_1") (pintype "passive"))
      (node (ref "C136") (pin "1") (pinfunction "1_1") (pintype "passive"))
      (node (ref "C137") (pin "1") (pinfunction "1_1") (pintype "passive"))
      (node (ref "C138") (pin "1") (pinfunction "1_1") (pintype "passive"))
      (node (ref "C166") (pin "1") (pinfunction "1_1") (pintype "passive"))
      (node (ref "C167") (pin "1") (pinfunction "1_1") (pintype "passive"))
      (node (ref "C21") (pin "1") (pinfunction "1_1") (pintype "passive"))
      (node (ref "C23") (pin "1") (pinfunction "1_1") (pintype "passive"))
      (node (ref "C25") (pin "1") (pinfunction "1_1") (pintype "passive"))
      (node (ref "C30") (pin "1") (pinfunction "1_1") (pintype "passive"))
      (node (ref "C38") (pin "1") (pinfunction "1_1") (pintype "passive"))
      (node (ref "C40") (pin "1") (pinfunction "1_1") (pintype "passive"))
      (node (ref "C50") (pin "1") (pinfunction "1_1") (pintype "passive"))
      (node (ref "C53") (pin "1") (pinfunction "1_1") (pintype "passive"))
      (node (ref "C54") (pin "1") (pinfunction "1_1") (pintype "passive"))
      (node (ref "C55") (pin "1") (pinfunction "1_1") (pintype "passive"))
      (node (ref "C56") (pin "1") (pinfunction "1_1") (pintype "passive"))
      (node (ref "C58") (pin "1") (pinfunction "1_1") (pintype "passive"))
      (node (ref "C59") (pin "1") (pinfunction "1_1") (pintype "passive"))
      (node (ref "C62") (pin "1") (pinfunction "1_1") (pintype "passive"))
      (node (ref "C65") (pin "1") (pinfunction "1_1") (pintype "passive"))
      (node (ref "C83") (pin "1") (pinfunction "1_1") (pintype "passive"))
      (node (ref "C84") (pin "1") (pinfunction "1_1") (pintype "passive"))
      (node (ref "CN1") (pin "B4") (pinfunction "GND_B_B4") (pintype "passive"))
      (node (ref "CN1") (pin "CH1") (pinfunction "CHASSIS1_CH1") (pintype "passive"))
      (node (ref "CN1") (pin "CH2") (pinfunction "CHASSIS2_CH2") (pintype "passive"))
      (node (ref "CN1") (pin "CH3") (pinfunction "CHASSIS3_CH3") (pintype "passive"))
      (node (ref "CN1") (pin "CH4") (pinfunction "CHASSIS4_CH4") (pintype "passive"))
      (node (ref "CN1") (pin "T4") (pinfunction "GND_T_T4") (pintype "passive"))
      (node (ref "CN5") (pin "B4") (pinfunction "GND_B_B4") (pintype "passive"))
      (node (ref "CN5") (pin "CH1") (pinfunction "CHASSIS1_CH1") (pintype "passive"))
      (node (ref "CN5") (pin "CH2") (pinfunction "CHASSIS2_CH2") (pintype "passive"))
      (node (ref "CN5") (pin "CH3") (pinfunction "CHASSIS3_CH3") (pintype "passive"))
      (node (ref "CN5") (pin "CH4") (pinfunction "CHASSIS4_CH4") (pintype "passive"))
      (node (ref "CN5") (pin "T4") (pinfunction "GND_T_T4") (pintype "passive"))
      (node (ref "CN7") (pin "A1") (pinfunction "GND1_A1") (pintype "passive"))
      (node (ref "CN7") (pin "A12") (pinfunction "GND2_A12") (pintype "passive"))
      (node (ref "CN7") (pin "B1") (pinfunction "GND3_B1") (pintype "passive"))
      (node (ref "CN7") (pin "B12") (pinfunction "GND4_B12") (pintype "passive"))
      (node (ref "CN7") (pin "SH1") (pinfunction "Shield1_SH1") (pintype "passive"))
      (node (ref "CN7") (pin "SH2") (pinfunction "Shield2_SH2") (pintype "passive"))
      (node (ref "CN7") (pin "SH3") (pinfunction "Shield3_SH3") (pintype "passive"))
      (node (ref "CN7") (pin "SH4") (pinfunction "Shield4_SH4") (pintype "passive"))
      (node (ref "LD1") (pin "2") (pintype "passive"))
      (node (ref "R129") (pin "1") (pinfunction "1_1") (pintype "passive"))
      (node (ref "R137") (pin "1") (pinfunction "1_1") (pintype "passive"))
      (node (ref "R139") (pin "1") (pinfunction "1_1") (pintype "passive"))
      (node (ref "R23") (pin "1") (pinfunction "1_1") (pintype "passive"))
      (node (ref "R24") (pin "1") (pinfunction "1_1") (pintype "passive"))
      (node (ref "R31") (pin "1") (pinfunction "1_1") (pintype "passive"))
      (node (ref "R36") (pin "1") (pinfunction "1_1") (pintype "passive"))
      (node (ref "R46") (pin "1") (pinfunction "1_1") (pintype "passive"))
      (node (ref "U1") (pin "3") (pinfunction "GND_3") (pintype "passive"))
      (node (ref "U11") (pin "1") (pinfunction "GND_1") (pintype "passive"))
      (node (ref "U12") (pin "10") (pinfunction "GND_10") (pintype "passive"))
      (node (ref "U12") (pin "22") (pinfunction "VSYS_22") (pintype "passive"))
      (node (ref "U12") (pin "ep") (pinfunction "EP_ep") (pintype "passive"))
      (node (ref "U17") (pin "3") (pinfunction "GND_3") (pintype "passive"))
      (node (ref "U2") (pin "3") (pinfunction "GND_3") (pintype "passive"))
      (node (ref "U24") (pin "2") (pinfunction "GND_2") (pintype "passive"))
      (node (ref "U25") (pin "2") (pinfunction "GND_2") (pintype "passive"))
      (node (ref "U27") (pin "2") (pinfunction "GND_2") (pintype "passive"))
      (node (ref "U28") (pin "2") (pinfunction "GND_2") (pintype "passive"))
      (node (ref "U29") (pin "3") (pinfunction "GND_3") (pintype "passive"))
      (node (ref "U3") (pin "1") (pinfunction "GND_1") (pintype "passive"))
      (node (ref "U30") (pin "2") (pinfunction "GND_2") (pintype "passive"))
      (node (ref "U6") (pin "3") (pinfunction "GND_3") (pintype "passive"))
      (node (ref "U7") (pin "11") (pinfunction "TEST_11") (pintype "input"))
      (node (ref "U7") (pin "37") (pinfunction "VSS(FLAG)_37") (pintype "power_in"))
      (node (ref "U9") (pin "3") (pinfunction "GND_3") (pintype "passive"))
      (node (ref "X1") (pin "2") (pinfunction "2_2") (pintype "passive"))
      (node (ref "X1") (pin "4") (pinfunction "4_4") (pintype "passive"))
    )
    (net (code "39") (name "Net-(C66-Pad2)") (class "Default")
      (node (ref "C66") (pin "2") (pinfunction "2_2") (pintype "passive"))
      (node (ref "R42") (pin "2") (pinfunction "2_2") (pintype "passive"))
      (node (ref "T1") (pin "1") (pinfunction "S_1") (pintype "passive"))
      (node (ref "T1") (pin "2") (pinfunction "S_2") (pintype "passive"))
      (node (ref "T1") (pin "3") (pinfunction "S_3") (pintype "passive"))
      (node (ref "T2") (pin "1") (pinfunction "S_1") (pintype "passive"))
      (node (ref "T2") (pin "2") (pinfunction "S_2") (pintype "passive"))
      (node (ref "T2") (pin "3") (pinfunction "S_3") (pintype "passive"))
    )
    (net (code "40") (name "Net-(CN1-VBUS_B)") (class "Default")
      (node (ref "C117") (pin "2") (pinfunction "2_2") (pintype "passive"))
      (node (ref "C118") (pin "2") (pinfunction "2_2") (pintype "passive"))
      (node (ref "CN1") (pin "B1") (pinfunction "VBUS_B_B1") (pintype "passive"))
      (node (ref "U24") (pin "1") (pinfunction "IO1_1") (pintype "passive"))
      (node (ref "U3") (pin "6") (pinfunction "OUT2_6") (pintype "passive"))
    )
    (net (code "41") (name "Net-(CN1-VBUS_T)") (class "Default")
      (node (ref "C123") (pin "2") (pinfunction "2_2") (pintype "passive"))
      (node (ref "C124") (pin "2") (pinfunction "2_2") (pintype "passive"))
      (node (ref "CN1") (pin "T1") (pinfunction "VBUS_T_T1") (pintype "passive"))
      (node (ref "U25") (pin "1") (pinfunction "IO1_1") (pintype "passive"))
      (node (ref "U3") (pin "7") (pinfunction "OUT1_7") (pintype "passive"))
    )
    (net (code "42") (name "Net-(CN5-VBUS_B)") (class "Default")
      (node (ref "C133") (pin "2") (pinfunction "2_2") (pintype "passive"))
      (node (ref "C136") (pin "2") (pinfunction "2_2") (pintype "passive"))
      (node (ref "CN5") (pin "B1") (pinfunction "VBUS_B_B1") (pintype "passive"))
      (node (ref "U11") (pin "6") (pinfunction "OUT2_6") (pintype "passive"))
      (node (ref "U27") (pin "1") (pinfunction "IO1_1") (pintype "passive"))
    )
    (net (code "43") (name "Net-(CN5-VBUS_T)") (class "Default")
      (node (ref "C137") (pin "2") (pinfunction "2_2") (pintype "passive"))
      (node (ref "C138") (pin "2") (pinfunction "2_2") (pintype "passive"))
      (node (ref "CN5") (pin "T1") (pinfunction "VBUS_T_T1") (pintype "passive"))
      (node (ref "U11") (pin "7") (pinfunction "OUT1_7") (pintype "passive"))
      (node (ref "U28") (pin "1") (pinfunction "IO1_1") (pintype "passive"))
    )
    (net (code "44") (name "Net-(CN7-CC1)") (class "Default")
      (node (ref "C84") (pin "2") (pinfunction "2_2") (pintype "passive"))
      (node (ref "CN7") (pin "A5") (pinfunction "CC1_A5") (pintype "passive"))
      (node (ref "R34") (pin "2") (pinfunction "2_2") (pintype "passive"))
      (node (ref "U12") (pin "2") (pinfunction "CC1_2") (pintype "passive"))
      (node (ref "U17") (pin "1") (pinfunction "IO1_1") (pintype "passive"))
    )
    (net (code "45") (name "Net-(CN7-CC2)") (class "Default")
      (node (ref "C83") (pin "2") (pinfunction "2_2") (pintype "passive"))
      (node (ref "CN7") (pin "B5") (pinfunction "CC2_B5") (pintype "passive"))
      (node (ref "R35") (pin "2") (pinfunction "2_2") (pintype "passive"))
      (node (ref "U12") (pin "4") (pinfunction "CC2_4") (pintype "passive"))
      (node (ref "U17") (pin "2") (pinfunction "IO2_2") (pintype "passive"))
    )
    (net (code "46") (name "Net-(CN7-VBUS1)") (class "Default")
      (node (ref "C166") (pin "2") (pinfunction "2_2") (pintype "passive"))
      (node (ref "C167") (pin "2") (pinfunction "2_2") (pintype "passive"))
      (node (ref "CN7") (pin "A4") (pinfunction "VBUS1_A4") (pintype "passive"))
      (node (ref "CN7") (pin "A9") (pinfunction "VBUS2_A9") (pintype "passive"))
      (node (ref "CN7") (pin "B4") (pinfunction "VBUS3_B4") (pintype "passive"))
      (node (ref "CN7") (pin "B9") (pinfunction "VBUS4_B9") (pintype "passive"))
      (node (ref "R150") (pin "1") (pinfunction "1_1") (pintype "passive"))
      (node (ref "U30") (pin "1") (pinfunction "IO1_1") (pintype "passive"))
    )
    (net (code "47") (name "Net-(LD1-Pad1)") (class "Default")
      (node (ref "LD1") (pin "1") (pintype "passive"))
      (node (ref "R21") (pin "1") (pinfunction "1_1") (pintype "passive"))
    )
    (net (code "48") (name "Net-(T1-G)") (class "Default")
      (node (ref "C66") (pin "1") (pinfunction "1_1") (pintype "passive"))
      (node (ref "R42") (pin "1") (pinfunction "1_1") (pintype "passive"))
      (node (ref "R43") (pin "1") (pinfunction "1_1") (pintype "passive"))
      (node (ref "T1") (pin "4") (pinfunction "G_4") (pintype "passive"))
      (node (ref "T2") (pin "4") (pinfunction "G_4") (pintype "passive"))
    )
    (net (code "49") (name "Net-(U7-CRFILT)") (class "Default")
      (node (ref "C25") (pin "2") (pinfunction "2_2") (pintype "passive"))
      (node (ref "U7") (pin "14") (pinfunction "CRFILT_14") (pintype "power_in"))
    )
    (net (code "50") (name "Net-(U7-HS_IND{slash}CFG_SEL1)") (class "Default")
      (node (ref "R139") (pin "2") (pinfunction "2_2") (pintype "passive"))
      (node (ref "R140") (pin "1") (pinfunction "1_1") (pintype "passive"))
      (node (ref "U7") (pin "25") (pinfunction "HS_IND/CFG_SEL1_25") (pintype "passive"))
    )
    (net (code "51") (name "Net-(U7-PLLFILT)") (class "Default")
      (node (ref "C53") (pin "2") (pinfunction "2_2") (pintype "passive"))
      (node (ref "U7") (pin "34") (pinfunction "PLLFILT_34") (pintype "power_in"))
    )
    (net (code "52") (name "Net-(U7-RBIAS)") (class "Default")
      (node (ref "R24") (pin "2") (pinfunction "2_2") (pintype "passive"))
      (node (ref "U7") (pin "35") (pinfunction "RBIAS_35") (pintype "passive"))
    )
    (net (code "53") (name "Net-(U7-SCL{slash}SMBCLK{slash}CFG_SEL0)") (class "Default")
      (node (ref "R134") (pin "1") (pinfunction "1_1") (pintype "passive"))
      (node (ref "R137") (pin "2") (pinfunction "2_2") (pintype "passive"))
      (node (ref "SB8") (pin "2") (pinfunction "2_2") (pintype "passive"))
      (node (ref "U7") (pin "24") (pinfunction "SCL/SMBCLK/CFG_SEL0_24") (pintype "bidirectional"))
    )
    (net (code "54") (name "Net-(U7-SDA{slash}SMBDATA{slash}NON_REM1)") (class "Default")
      (node (ref "R127") (pin "1") (pinfunction "1_1") (pintype "passive"))
      (node (ref "R129") (pin "2") (pinfunction "2_2") (pintype "passive"))
      (node (ref "SB7") (pin "2") (pinfunction "2_2") (pintype "passive"))
      (node (ref "U7") (pin "22") (pinfunction "SDA/SMBDATA/NON_REM1_22") (pintype "bidirectional"))
    )
    (net (code "55") (name "Net-(U7-SUSP_IND{slash}L_PWR{slash}NON_REM0)") (class "Default")
      (node (ref "R21") (pin "2") (pinfunction "2_2") (pintype "passive"))
      (node (ref "R23") (pin "2") (pinfunction "2_2") (pintype "passive"))
      (node (ref "U7") (pin "28") (pinfunction "SUSP_IND/L_PWR/NON_REM0_28") (pintype "passive"))
    )
    (net (code "56") (name "Net-(U7-VBUS_DET)") (class "Default")
      (node (ref "R18") (pin "1") (pinfunction "1_1") (pintype "passive"))
      (node (ref "U7") (pin "27") (pinfunction "VBUS_DET_27") (pintype "passive"))
    )
    (net (code "57") (name "Net-(U7-XTAL1{slash}CKIN)") (class "Default")
      (node (ref "C59") (pin "2") (pinfunction "2_2") (pintype "passive"))
      (node (ref "U7") (pin "33") (pinfunction "XTAL1/CKIN_33") (pintype "input"))
      (node (ref "X1") (pin "1") (pinfunction "1_1") (pintype "passive"))
    )
    (net (code "58") (name "Net-(U7-XTAL2{slash}CKIN_EN)") (class "Default")
      (node (ref "C58") (pin "2") (pinfunction "2_2") (pintype "passive"))
      (node (ref "U7") (pin "32") (pinfunction "XTAL2/CKIN_EN_32") (pintype "output"))
      (node (ref "X1") (pin "3") (pinfunction "3_3") (pintype "passive"))
    )
    (net (code "59") (name "Net-(U7-~{RESET})") (class "Default")
      (node (ref "R600") (pin "2") (pinfunction "2_2") (pintype "passive"))
      (node (ref "U7") (pin "26") (pinfunction "~{RESET}_26") (pintype "input"))
    )
    (net (code "60") (name "Net-(U11-IN)") (class "Default")
      (node (ref "L8") (pin "2") (pinfunction "2_2") (pintype "passive"))
      (node (ref "U11") (pin "2") (pinfunction "IN_2") (pintype "passive"))
      (node (ref "U3") (pin "2") (pinfunction "IN_2") (pintype "passive"))
    )
    (net (code "61") (name "Net-(U12-ADDR0)") (class "Default")
      (node (ref "R46") (pin "2") (pinfunction "2_2") (pintype "passive"))
      (node (ref "U12") (pin "13") (pinfunction "ADDR0_13") (pintype "passive"))
    )
    (net (code "62") (name "Net-(U12-ATTACH)") (class "Default")
      (node (ref "TP16") (pin "1") (pinfunction "1_1") (pintype "passive"))
      (node (ref "U12") (pin "12") (pinfunction "ATTACH_12") (pintype "passive"))
    )
    (net (code "63") (name "Net-(U12-CC1DB)") (class "Default")
      (node (ref "R34") (pin "1") (pinfunction "1_1") (pintype "passive"))
      (node (ref "U12") (pin "1") (pinfunction "CC1DB_1") (pintype "passive"))
    )
    (net (code "64") (name "Net-(U12-CC2DB)") (class "Default")
      (node (ref "R35") (pin "1") (pinfunction "1_1") (pintype "passive"))
      (node (ref "U12") (pin "5") (pinfunction "CC2DB_5") (pintype "passive"))
    )
    (net (code "65") (name "Net-(U12-DEBUG1)") (class "Default")
      (node (ref "TP17") (pin "1") (pinfunction "1_1") (pintype "passive"))
      (node (ref "U12") (pin "14") (pinfunction "DEBUG1_14") (pintype "passive"))
    )
    (net (code "66") (name "Net-(U12-DEBUG2)") (class "Default")
      (node (ref "TP18") (pin "1") (pinfunction "1_1") (pintype "passive"))
      (node (ref "U12") (pin "15") (pinfunction "DEBUG2_15") (pintype "passive"))
    )
    (net (code "67") (name "Net-(U12-RESET)") (class "Default")
      (node (ref "R36") (pin "2") (pinfunction "2_2") (pintype "passive"))
      (node (ref "U12") (pin "6") (pinfunction "RESET_6") (pintype "passive"))
    )
    (net (code "68") (name "Net-(U12-VBUS_EN_SRC)") (class "Default")
      (node (ref "R43") (pin "2") (pinfunction "2_2") (pintype "passive"))
      (node (ref "U12") (pin "20") (pinfunction "VBUS_EN_SRC_20") (pintype "passive"))
    )
    (net (code "69") (name "Net-(U12-VBUS_SENSE)") (class "Default")
      (node (ref "R150") (pin "2") (pinfunction "2_2") (pintype "passive"))
      (node (ref "T2") (pin "5") (pinfunction "D_5") (pintype "passive"))
      (node (ref "T2") (pin "6") (pinfunction "D_6") (pintype "passive"))
      (node (ref "T2") (pin "7") (pinfunction "D_7") (pintype "passive"))
      (node (ref "T2") (pin "8") (pinfunction "D_8") (pintype "passive"))
      (node (ref "U12") (pin "18") (pinfunction "VBUS_SENSE_18") (pintype "passive"))
    )
    (net (code "70") (name "Net-(U12-VBUS_VALID)") (class "Default")
      (node (ref "TP15") (pin "1") (pinfunction "1_1") (pintype "passive"))
      (node (ref "U12") (pin "11") (pinfunction "VBUS_VALID_11") (pintype "passive"))
    )
    (net (code "71") (name "Net-(U12-VCONN)") (class "Default")
      (node (ref "R31") (pin "2") (pinfunction "2_2") (pintype "passive"))
      (node (ref "R32") (pin "1") (pinfunction "1_1") (pintype "passive"))
      (node (ref "U12") (pin "3") (pinfunction "VCONN_3") (pintype "passive"))
    )
    (net (code "72") (name "Net-(U12-VREG_1V2)") (class "Default")
      (node (ref "C65") (pin "2") (pinfunction "2_2") (pintype "passive"))
      (node (ref "U12") (pin "21") (pinfunction "VREG_1V2_21") (pintype "passive"))
    )
    (net (code "73") (name "Net-(U12-VREG_2V7)") (class "Default")
      (node (ref "C62") (pin "2") (pinfunction "2_2") (pintype "passive"))
      (node (ref "U12") (pin "23") (pinfunction "VREG_2V7_23") (pintype "passive"))
    )
    (net (code "74") (name "unconnected-(CN7-RX1+-PadB11)") (class "Default")
      (node (ref "CN7") (pin "B11") (pinfunction "RX1+_B11") (pintype "passive+no_connect"))
    )
    (net (code "75") (name "unconnected-(CN7-RX1--PadB10)") (class "Default")
      (node (ref "CN7") (pin "B10") (pinfunction "RX1-_B10") (pintype "passive+no_connect"))
    )
    (net (code "76") (name "unconnected-(CN7-RX2+-PadA11)") (class "Default")
      (node (ref "CN7") (pin "A11") (pinfunction "RX2+_A11") (pintype "passive+no_connect"))
    )
    (net (code "77") (name "unconnected-(CN7-RX2--PadA10)") (class "Default")
      (node (ref "CN7") (pin "A10") (pinfunction "RX2-_A10") (pintype "passive+no_connect"))
    )
    (net (code "78") (name "unconnected-(CN7-SBU1-PadA8)") (class "Default")
      (node (ref "CN7") (pin "A8") (pinfunction "SBU1_A8") (pintype "passive+no_connect"))
    )
    (net (code "79") (name "unconnected-(CN7-SBU2-PadB8)") (class "Default")
      (node (ref "CN7") (pin "B8") (pinfunction "SBU2_B8") (pintype "passive+no_connect"))
    )
    (net (code "80") (name "unconnected-(CN7-TX1+-PadA2)") (class "Default")
      (node (ref "CN7") (pin "A2") (pinfunction "TX1+_A2") (pintype "passive+no_connect"))
    )
    (net (code "81") (name "unconnected-(CN7-TX1--PadA3)") (class "Default")
      (node (ref "CN7") (pin "A3") (pinfunction "TX1-_A3") (pintype "passive+no_connect"))
    )
    (net (code "82") (name "unconnected-(CN7-TX2+-PadB2)") (class "Default")
      (node (ref "CN7") (pin "B2") (pinfunction "TX2+_B2") (pintype "passive+no_connect"))
    )
    (net (code "83") (name "unconnected-(CN7-TX2--PadB3)") (class "Default")
      (node (ref "CN7") (pin "B3") (pinfunction "TX2-_B3") (pintype "passive+no_connect"))
    )
    (net (code "84") (name "unconnected-(U1-NC-Pad4)") (class "Default")
      (node (ref "U1") (pin "4") (pinfunction "NC_4") (pintype "passive+no_connect"))
    )
    (net (code "85") (name "unconnected-(U2-NC-Pad4)") (class "Default")
      (node (ref "U2") (pin "4") (pinfunction "NC_4") (pintype "passive+no_connect"))
    )
    (net (code "86") (name "unconnected-(U6-NC-Pad4)") (class "Default")
      (node (ref "U6") (pin "4") (pinfunction "NC_4") (pintype "passive+no_connect"))
    )
    (net (code "87") (name "unconnected-(U9-NC-Pad4)") (class "Default")
      (node (ref "U9") (pin "4") (pinfunction "NC_4") (pintype "passive+no_connect"))
    )
    (net (code "88") (name "unconnected-(U12-A_B_SIDE-Pad17)") (class "Default")
      (node (ref "U12") (pin "17") (pinfunction "A_B_SIDE_17") (pintype "passive+no_connect"))
    )
    (net (code "89") (name "unconnected-(U12-NC-Pad16)") (class "Default")
      (node (ref "U12") (pin "16") (pinfunction "NC_16") (pintype "passive+no_connect"))
    )
    (net (code "90") (name "unconnected-(U12-VBUS_EN_SNK-Pad19)") (class "Default")
      (node (ref "U12") (pin "19") (pinfunction "VBUS_EN_SNK_19") (pintype "passive+no_connect"))
    )
    (net (code "91") (name "unconnected-(U29-NC-Pad4)") (class "Default")
      (node (ref "U29") (pin "4") (pinfunction "NC_4") (pintype "passive+no_connect"))
    )
  )
)
